# esp_stm_v1.net
KiCad netlist of a schematic drawn in Altium Designer
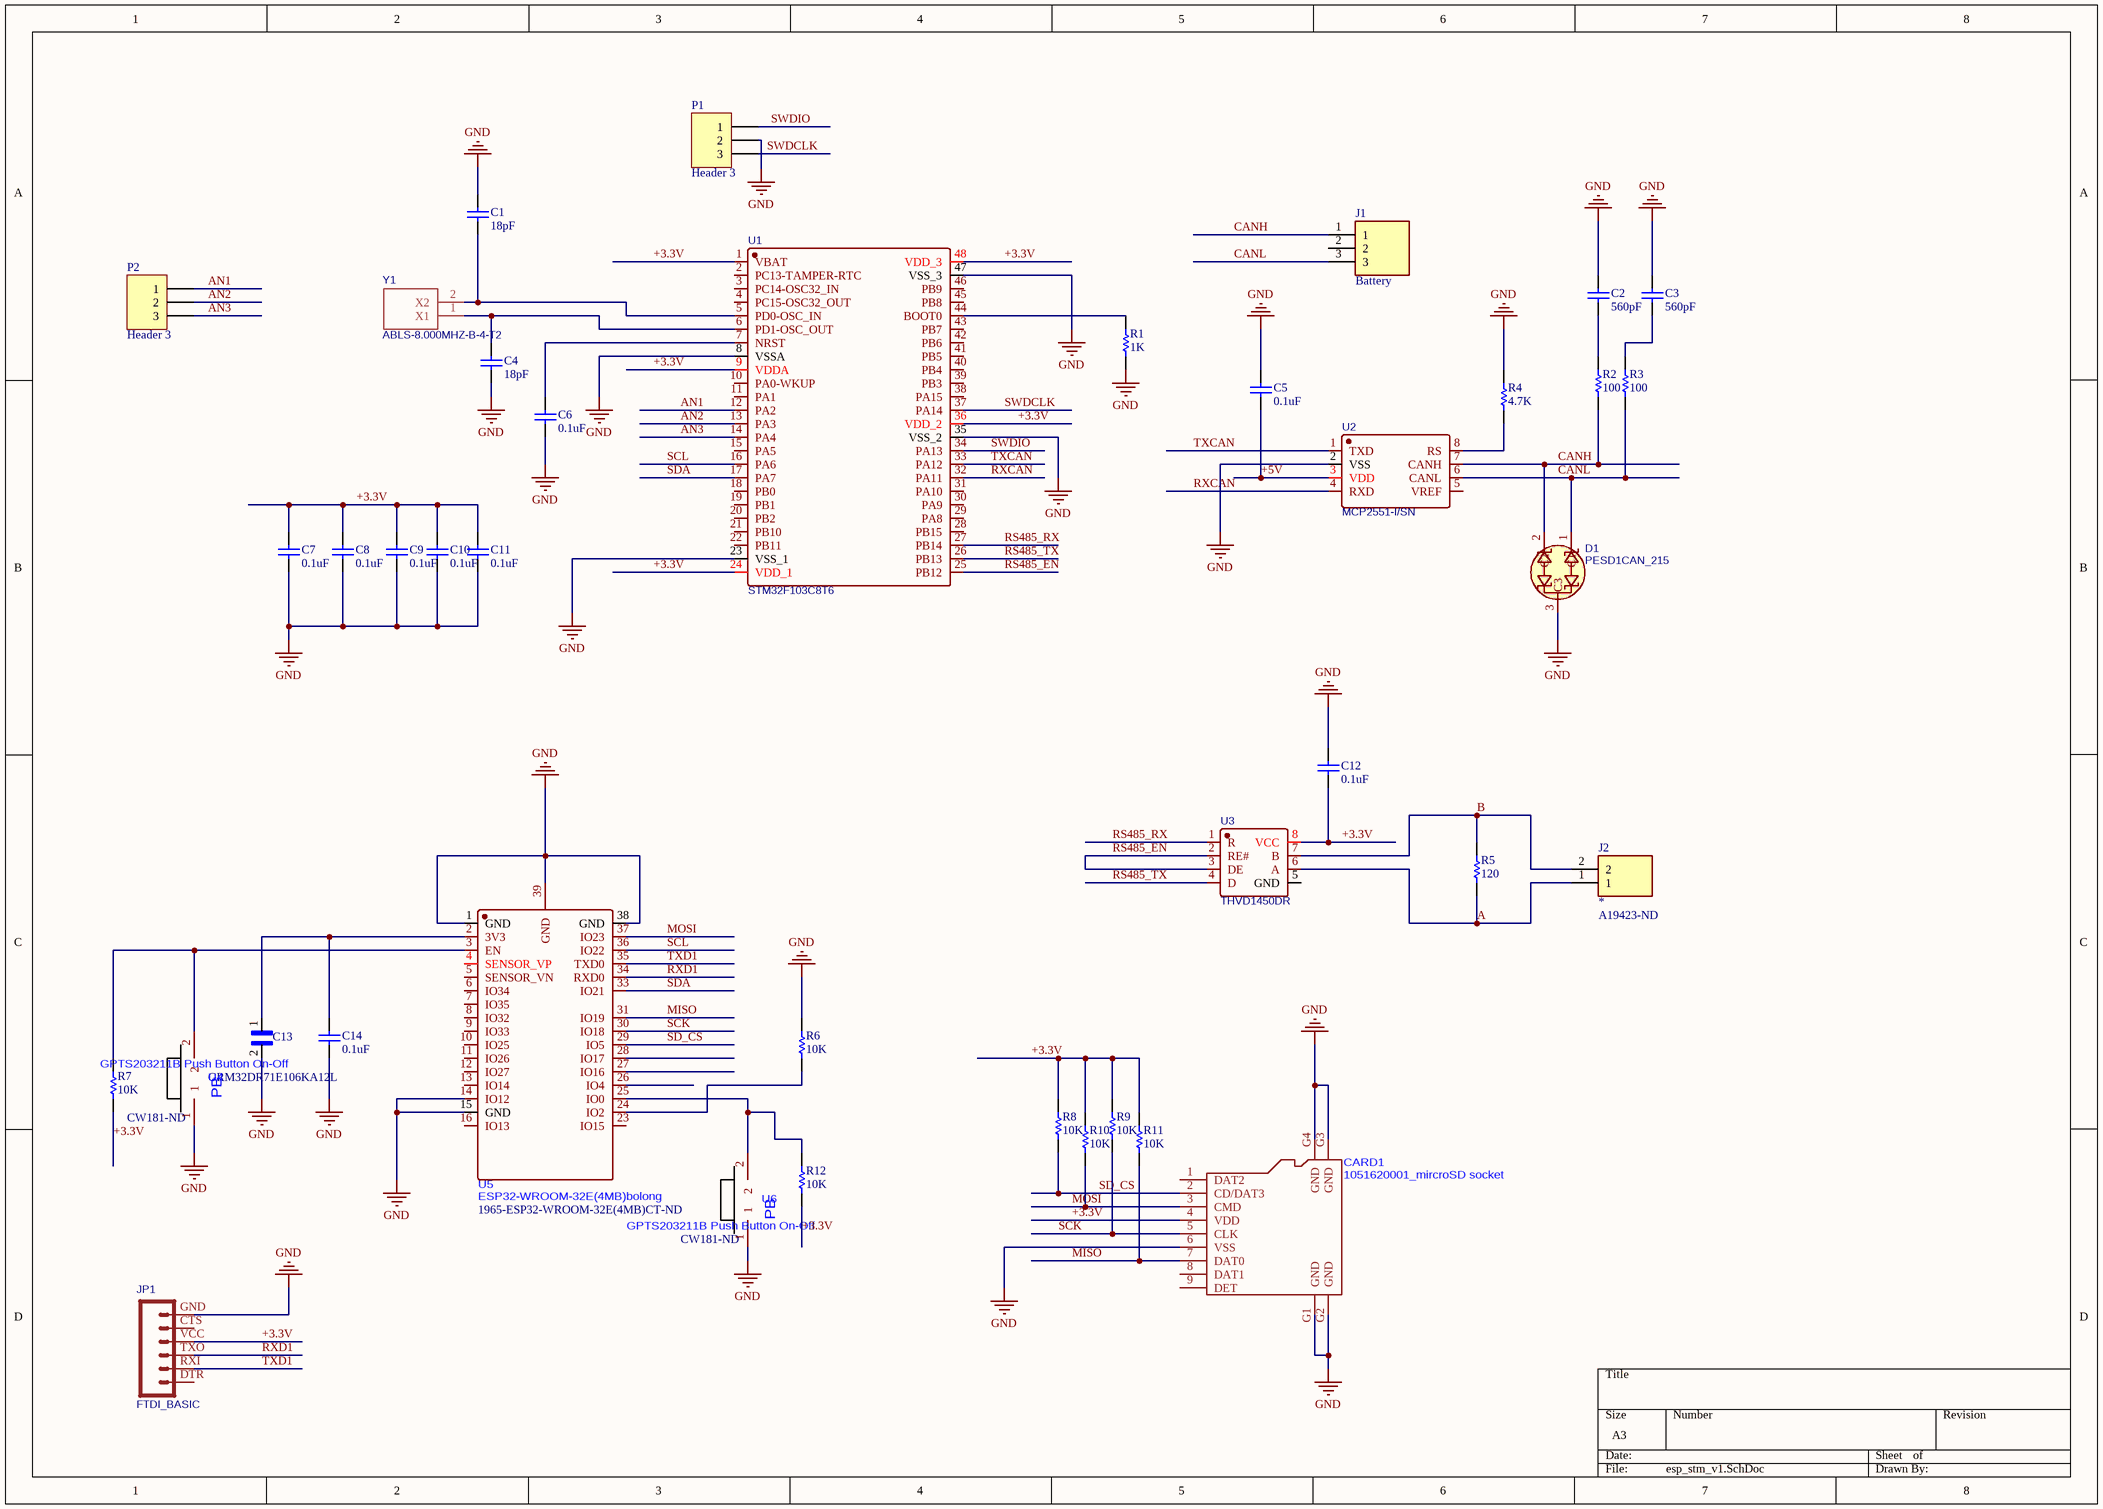
[diagram p0: esp_stm_v1.SchDoc]

(export (version "E")
  (design (tool "Eeschema 10.0.6"))
  (components
    (comp (ref "C1")
      (value "18pF")
      (footprint "1206")
      (description "Capacitor")
      (fields
        (field (name "MANUFACTURE PART NUMBER") "885012208087")
        (field (name "VENDOR PART NUMBER") "732-8127-1-ND")
      )
      (libsource (lib "Miscellaneous Devices") (part "Cap"))
    )
    (comp (ref "C2")
      (value "560pF")
      (footprint "library_v3:SMD-1206-RES")
      (description "Capacitor")
      (fields
        (field (name "MANUFACTURE PART NUMBER") "885012208087")
        (field (name "VENDOR PART NUMBER") "732-8127-1-ND")
      )
      (libsource (lib "Miscellaneous Devices") (part "Cap"))
    )
    (comp (ref "C3")
      (value "560pF")
      (footprint "library_v3:SMD-1206-RES")
      (description "Capacitor")
      (fields
        (field (name "MANUFACTURE PART NUMBER") "885012208087")
        (field (name "VENDOR PART NUMBER") "732-8127-1-ND")
      )
      (libsource (lib "Miscellaneous Devices") (part "Cap"))
    )
    (comp (ref "C4")
      (value "18pF")
      (footprint "1206")
      (description "Capacitor")
      (fields
        (field (name "MANUFACTURE PART NUMBER") "885012208087")
        (field (name "VENDOR PART NUMBER") "732-8127-1-ND")
      )
      (libsource (lib "Miscellaneous Devices") (part "Cap"))
    )
    (comp (ref "C5")
      (value "0.1uF")
      (footprint "library_v3:SMD-1206-RES")
      (description "Capacitor")
      (fields
        (field (name "MANUFACTURE PART NUMBER") "885012208087")
        (field (name "VENDOR PART NUMBER") "732-8127-1-ND")
      )
      (libsource (lib "Miscellaneous Devices") (part "Cap"))
    )
    (comp (ref "C6")
      (value "0.1uF")
      (footprint "1206")
      (description "Capacitor")
      (fields
        (field (name "MANUFACTURE PART NUMBER") "885012208087")
        (field (name "VENDOR PART NUMBER") "732-8127-1-ND")
      )
      (libsource (lib "Miscellaneous Devices") (part "Cap"))
    )
    (comp (ref "C7")
      (value "0.1uF")
      (footprint "1206")
      (description "Capacitor")
      (fields
        (field (name "MANUFACTURE PART NUMBER") "885012208087")
        (field (name "VENDOR PART NUMBER") "732-8127-1-ND")
      )
      (libsource (lib "Miscellaneous Devices") (part "Cap"))
    )
    (comp (ref "C8")
      (value "0.1uF")
      (footprint "1206")
      (description "Capacitor")
      (fields
        (field (name "MANUFACTURE PART NUMBER") "885012208087")
        (field (name "VENDOR PART NUMBER") "732-8127-1-ND")
      )
      (libsource (lib "Miscellaneous Devices") (part "Cap"))
    )
    (comp (ref "C9")
      (value "0.1uF")
      (footprint "1206")
      (description "Capacitor")
      (fields
        (field (name "MANUFACTURE PART NUMBER") "885012208087")
        (field (name "VENDOR PART NUMBER") "732-8127-1-ND")
      )
      (libsource (lib "Miscellaneous Devices") (part "Cap"))
    )
    (comp (ref "C10")
      (value "0.1uF")
      (footprint "1206")
      (description "Capacitor")
      (fields
        (field (name "MANUFACTURE PART NUMBER") "885012208087")
        (field (name "VENDOR PART NUMBER") "732-8127-1-ND")
      )
      (libsource (lib "Miscellaneous Devices") (part "Cap"))
    )
    (comp (ref "C11")
      (value "0.1uF")
      (footprint "1206")
      (description "Capacitor")
      (fields
        (field (name "MANUFACTURE PART NUMBER") "885012208087")
        (field (name "VENDOR PART NUMBER") "732-8127-1-ND")
      )
      (libsource (lib "Miscellaneous Devices") (part "Cap"))
    )
    (comp (ref "C12")
      (value "0.1uF")
      (footprint "SMD-1206-RES")
      (description "Capacitor")
      (fields
        (field (name "MANUFACTURE PART NUMBER") "885012208087")
        (field (name "VENDOR PART NUMBER") "732-8127-1-ND")
      )
      (libsource (lib "Miscellaneous Devices") (part "Cap"))
    )
    (comp (ref "C13")
      (value "GRM32DR71E106KA12L")
      (footprint "CAPC3225X270N")
      (description "SMD Capacitor X7R_EIA_ with Capacitance: 10uF Tol. 10%. Rated Voltage: 25Vdc")
      (fields (field (name "MF") "Murata Electronics"))
      (libsource (lib "library_v3") (part "GRM32DR71E106KA12L"))
    )
    (comp (ref "C14")
      (value "0.1uF")
      (footprint "1206")
      (description "Capacitor")
      (fields
        (field (name "MANUFACTURE PART NUMBER") "885012208087")
        (field (name "VENDOR PART NUMBER") "732-8127-1-ND")
      )
      (libsource (lib "Miscellaneous Devices") (part "Cap"))
    )
    (comp (ref "CARD1")
      (value "1051620001_mircroSD socket")
      (footprint "1051620001 MOLEX")
      (libsource (lib "comp_1") (part "1051620001_mircroSD socket"))
    )
    (comp (ref "D1")
      (value "PESD1CAN_215")
      (footprint "SOT-23-3")
      (fields (field (name "MANUFACTURER") "Nexperia USA Inc.") (field (name "CONTRIBUTOR") "carlo1300"))
      (libsource (lib "comp_1") (part "PESD1CAN_215"))
    )
    (comp (ref "J1")
      (value "PR20203VBNN")
      (footprint "TE_640456-3")
      (description "Connector Header Through Hole 3 position 0.100 _2.54mm_")
      (fields
        (field (name "DIGI-KEY_PART_NUMBER") "1849-1003-ND")
        (field (name "MF") "METZ CONNECT USA Inc.")
        (field (name "COMMENT_1") "Battery")
      )
      (libsource (lib "library_v3") (part "640456-3"))
    )
    (comp (ref "J2")
      (value "640454-2")
      (footprint "TE_640454-2")
      (description "02P MTA100 HDR ASSY SQ STR POL")
      (fields
        (field (name "MF") "TE Connectivity")
        (field (name "DIGI-KEY_PART_NUMBER") "A19439-ND")
        (field (name "COMMENT_1") "*")
        (field (name "SUPPLIER PART NUMBER 1") "A19423-ND")
      )
      (libsource (lib "library_v3") (part "640454-2"))
    )
    (comp (ref "JP1")
      (value "FTDI_BASIC")
      (footprint "FTDI_BASIC")
      (fields (field (name "BOM_MANUFACTURER PART") "?") (field (name "CONTRIBUTOR") "SparkFun"))
      (libsource (lib "library_v3") (part "FTDI_BASIC"))
    )
    (comp (ref "P1")
      (value "Header 3")
      (footprint "HDR1X3")
      (description "Header, 3-Pin")
      (fields (field (name "PUBLISHER") "Altium Limited"))
      (libsource (lib "Miscellaneous Connectors") (part "Header 3"))
    )
    (comp (ref "P2")
      (value "Header 3")
      (footprint "HDR1X3")
      (description "Header, 3-Pin")
      (fields (field (name "PUBLISHER") "Altium Limited"))
      (libsource (lib "Miscellaneous Connectors") (part "Header 3"))
    )
    (comp (ref "R1")
      (value "1K")
      (footprint "1206")
      (description "Semiconductor Resistor")
      (fields
        (field (name "MANUFACTURE PART NUMBER") "RC1206JR-0710KL")
        (field (name "VENDOR PART NUMBER") "311-10KERCT-ND")
      )
      (libsource (lib "Miscellaneous Devices") (part "Res Semi"))
    )
    (comp (ref "R2")
      (value "100")
      (footprint "library_v3:SMD-1206-RES")
      (description "Semiconductor Resistor")
      (fields
        (field (name "MANUFACTURE PART NUMBER") "RC1206JR-0710KL")
        (field (name "VENDOR PART NUMBER") "311-10KERCT-ND")
      )
      (libsource (lib "Miscellaneous Devices") (part "Res Semi"))
    )
    (comp (ref "R3")
      (value "100")
      (footprint "library_v3:SMD-1206-RES")
      (description "Semiconductor Resistor")
      (fields
        (field (name "MANUFACTURE PART NUMBER") "RC1206JR-0710KL")
        (field (name "VENDOR PART NUMBER") "311-10KERCT-ND")
      )
      (libsource (lib "Miscellaneous Devices") (part "Res Semi"))
    )
    (comp (ref "R4")
      (value "4.7K")
      (footprint "library_v3:SMD-1206-RES")
      (description "Semiconductor Resistor")
      (fields
        (field (name "MANUFACTURE PART NUMBER") "RC1206JR-0710KL")
        (field (name "VENDOR PART NUMBER") "311-10KERCT-ND")
      )
      (libsource (lib "Miscellaneous Devices") (part "Res Semi"))
    )
    (comp (ref "R5")
      (value "120")
      (footprint "SMD-1206-RES")
      (description "Semiconductor Resistor")
      (fields
        (field (name "MANUFACTURE PART NUMBER") "RC1206JR-0710KL")
        (field (name "VENDOR PART NUMBER") "311-10KERCT-ND")
      )
      (libsource (lib "*") (part "Res Semi"))
    )
    (comp (ref "R6")
      (value "10K")
      (footprint "1206")
      (description "Semiconductor Resistor")
      (fields
        (field (name "MANUFACTURE PART NUMBER") "RC1206JR-0710KL")
        (field (name "VENDOR PART NUMBER") "311-10KERCT-ND")
      )
      (libsource (lib "Miscellaneous Devices") (part "Res Semi"))
    )
    (comp (ref "R7")
      (value "10K")
      (footprint "1206")
      (description "Semiconductor Resistor")
      (fields
        (field (name "MANUFACTURE PART NUMBER") "RC1206JR-0710KL")
        (field (name "VENDOR PART NUMBER") "311-10KERCT-ND")
      )
      (libsource (lib "Miscellaneous Devices") (part "Res Semi"))
    )
    (comp (ref "R8")
      (value "10K")
      (footprint "1206")
      (description "Semiconductor Resistor")
      (fields
        (field (name "MANUFACTURE PART NUMBER") "RC1206JR-0710KL")
        (field (name "VENDOR PART NUMBER") "311-10KERCT-ND")
      )
      (libsource (lib "Miscellaneous Devices") (part "Res Semi"))
    )
    (comp (ref "R9")
      (value "10K")
      (footprint "1206")
      (description "Semiconductor Resistor")
      (fields
        (field (name "MANUFACTURE PART NUMBER") "RC1206JR-0710KL")
        (field (name "VENDOR PART NUMBER") "311-10KERCT-ND")
      )
      (libsource (lib "Miscellaneous Devices") (part "Res Semi"))
    )
    (comp (ref "R10")
      (value "10K")
      (footprint "1206")
      (description "Semiconductor Resistor")
      (fields
        (field (name "MANUFACTURE PART NUMBER") "RC1206JR-0710KL")
        (field (name "VENDOR PART NUMBER") "311-10KERCT-ND")
      )
      (libsource (lib "Miscellaneous Devices") (part "Res Semi"))
    )
    (comp (ref "R11")
      (value "10K")
      (footprint "1206")
      (description "Semiconductor Resistor")
      (fields
        (field (name "MANUFACTURE PART NUMBER") "RC1206JR-0710KL")
        (field (name "VENDOR PART NUMBER") "311-10KERCT-ND")
      )
      (libsource (lib "Miscellaneous Devices") (part "Res Semi"))
    )
    (comp (ref "R12")
      (value "10K")
      (footprint "1206")
      (description "Semiconductor Resistor")
      (fields
        (field (name "MANUFACTURE PART NUMBER") "RC1206JR-0710KL")
        (field (name "VENDOR PART NUMBER") "311-10KERCT-ND")
      )
      (libsource (lib "Miscellaneous Devices") (part "Res Semi"))
    )
    (comp (ref "U1")
      (value "STM32F103C8T6")
      (footprint "LQFP-48_L7.0-W7.0-P0.50-LS9.0-BL")
      (fields (field (name "MANUFACTURER") "ST(意法半导体)"))
      (libsource (lib "component_lib_v1") (part "STM32F103C8T6"))
    )
    (comp (ref "U2")
      (value "MCP2551-I/SN")
      (footprint "SOIC8-1.27-5X4MM")
      (fields (field (name "BOM_SUPPLIER PART") "C7376"))
      (libsource (lib "comp_1") (part "MCP2551-I/SN"))
    )
    (comp (ref "U3")
      (value "THVD1450DR")
      (footprint "SOIC-8_L4.9-W3.9-P1.27-LS6.0-BL")
      (fields (field (name "MANUFACTURER") "TI(????)") (field (name "CONTRIBUTOR") "LCSC"))
      (libsource (lib "component_lib_v1") (part "THVD1450DR"))
    )
    (comp (ref "U4")
      (value "GPTS203211B Push Button On-Off")
      (footprint "GPTS203211B-PUSHBUTTON-ON-OFF")
      (fields (field (name "SUPPLIER PART NUMBER 1") "CW181-ND"))
      (libsource (lib "comp_1") (part "GPTS203211B Push Button On-Off"))
    )
    (comp (ref "U5")
      (value "ESP32-WROOM-32E(4MB)bolong")
      (footprint "WIFI-SMD_ESP32-WROOM-32E")
      (fields (field (name "SUPPLIER PART NUMBER 1") "1965-ESP32-WROOM-32E(4MB)CT-ND"))
      (libsource (lib "comp_1") (part "ESP32-WROOM-32E(4MB)bolong"))
    )
    (comp (ref "U6")
      (value "GPTS203211B Push Button On-Off")
      (footprint "GPTS203211B-PUSHBUTTON-ON-OFF")
      (fields (field (name "SUPPLIER PART NUMBER 1") "CW181-ND"))
      (libsource (lib "comp_1") (part "GPTS203211B Push Button On-Off"))
    )
    (comp (ref "Y1")
      (value "ABLS-8.000MHZ-B-4-T2")
      (footprint "ABLS8000MHZB4T2")
      (fields (field (name "CONTRIBUTOR") "Metin Akin"))
      (libsource (lib "library_v3") (part "ABLS-8.000MHZ-B-4-T2"))
    )
  )
  (nets
    (net (code "1") (name "/+3.3V") (class "Default")
      (node (ref "C10") (pin "1") (pinfunction "1_1") (pintype "passive"))
      (node (ref "C11") (pin "1") (pinfunction "1_1") (pintype "passive"))
      (node (ref "C12") (pin "2") (pinfunction "2_2") (pintype "passive"))
      (node (ref "C7") (pin "1") (pinfunction "1_1") (pintype "passive"))
      (node (ref "C8") (pin "1") (pinfunction "1_1") (pintype "passive"))
      (node (ref "C9") (pin "1") (pinfunction "1_1") (pintype "passive"))
      (node (ref "CARD1") (pin "4") (pinfunction "VDD_4") (pintype "passive"))
      (node (ref "JP1") (pin "VCC") (pinfunction "4_VCC") (pintype "passive"))
      (node (ref "R10") (pin "1") (pinfunction "1_1") (pintype "passive"))
      (node (ref "R11") (pin "1") (pinfunction "1_1") (pintype "passive"))
      (node (ref "R12") (pin "2") (pinfunction "2_2") (pintype "passive"))
      (node (ref "R7") (pin "2") (pinfunction "2_2") (pintype "passive"))
      (node (ref "R8") (pin "1") (pinfunction "1_1") (pintype "passive"))
      (node (ref "R9") (pin "1") (pinfunction "1_1") (pintype "passive"))
      (node (ref "U1") (pin "1") (pinfunction "VBAT_1") (pintype "passive"))
      (node (ref "U1") (pin "24") (pinfunction "VDD_1_24") (pintype "passive"))
      (node (ref "U1") (pin "36") (pinfunction "VDD_2_36") (pintype "passive"))
      (node (ref "U1") (pin "48") (pinfunction "VDD_3_48") (pintype "passive"))
      (node (ref "U1") (pin "9") (pinfunction "VDDA_9") (pintype "passive"))
      (node (ref "U3") (pin "8") (pinfunction "VCC_8") (pintype "passive"))
    )
    (net (code "2") (name "/+5V") (class "Default")
      (node (ref "C5") (pin "2") (pinfunction "2_2") (pintype "passive"))
      (node (ref "U2") (pin "3") (pinfunction "VDD_3") (pintype "passive"))
    )
    (net (code "3") (name "/A") (class "Default")
      (node (ref "J2") (pin "1") (pinfunction "1_1") (pintype "passive"))
      (node (ref "R5") (pin "2") (pinfunction "2_2") (pintype "passive"))
      (node (ref "U3") (pin "6") (pinfunction "A_6") (pintype "passive"))
    )
    (net (code "4") (name "/AN1") (class "Default")
      (node (ref "P2") (pin "1") (pinfunction "1_1") (pintype "passive"))
      (node (ref "U1") (pin "12") (pinfunction "PA2_12") (pintype "passive"))
    )
    (net (code "5") (name "/AN2") (class "Default")
      (node (ref "P2") (pin "2") (pinfunction "2_2") (pintype "passive"))
      (node (ref "U1") (pin "13") (pinfunction "PA3_13") (pintype "passive"))
    )
    (net (code "6") (name "/AN3") (class "Default")
      (node (ref "P2") (pin "3") (pinfunction "3_3") (pintype "passive"))
      (node (ref "U1") (pin "14") (pinfunction "PA4_14") (pintype "passive"))
    )
    (net (code "7") (name "/B") (class "Default")
      (node (ref "J2") (pin "2") (pinfunction "2_2") (pintype "passive"))
      (node (ref "R5") (pin "1") (pinfunction "1_1") (pintype "passive"))
      (node (ref "U3") (pin "7") (pinfunction "B_7") (pintype "passive"))
    )
    (net (code "8") (name "/CANH") (class "Default")
      (node (ref "D1") (pin "2") (pinfunction "C2_2") (pintype "passive"))
      (node (ref "J1") (pin "1") (pinfunction "1_1") (pintype "passive"))
      (node (ref "R2") (pin "1") (pinfunction "1_1") (pintype "passive"))
      (node (ref "U2") (pin "7") (pinfunction "CANH_7") (pintype "passive"))
    )
    (net (code "9") (name "/CANL") (class "Default")
      (node (ref "D1") (pin "1") (pinfunction "C1_1") (pintype "passive"))
      (node (ref "J1") (pin "3") (pinfunction "3_3") (pintype "passive"))
      (node (ref "R3") (pin "1") (pinfunction "1_1") (pintype "passive"))
      (node (ref "U2") (pin "6") (pinfunction "CANL_6") (pintype "passive"))
    )
    (net (code "10") (name "/MISO") (class "Default")
      (node (ref "CARD1") (pin "7") (pinfunction "DAT0_7") (pintype "passive"))
      (node (ref "R11") (pin "2") (pinfunction "2_2") (pintype "passive"))
      (node (ref "U5") (pin "31") (pinfunction "IO19_31") (pintype "passive"))
    )
    (net (code "11") (name "/MOSI") (class "Default")
      (node (ref "CARD1") (pin "3") (pinfunction "CMD_3") (pintype "passive"))
      (node (ref "R10") (pin "2") (pinfunction "2_2") (pintype "passive"))
      (node (ref "U5") (pin "37") (pinfunction "IO23_37") (pintype "passive"))
    )
    (net (code "12") (name "/RS485_EN") (class "Default")
      (node (ref "U1") (pin "25") (pinfunction "PB12_25") (pintype "passive"))
      (node (ref "U3") (pin "2") (pinfunction "RE#_2") (pintype "passive"))
      (node (ref "U3") (pin "3") (pinfunction "DE_3") (pintype "passive"))
    )
    (net (code "13") (name "/RS485_RX") (class "Default")
      (node (ref "U1") (pin "27") (pinfunction "PB14_27") (pintype "passive"))
      (node (ref "U3") (pin "1") (pinfunction "R_1") (pintype "passive"))
    )
    (net (code "14") (name "/RS485_TX") (class "Default")
      (node (ref "U1") (pin "26") (pinfunction "PB13_26") (pintype "passive"))
      (node (ref "U3") (pin "4") (pinfunction "D_4") (pintype "passive"))
    )
    (net (code "15") (name "/RXCAN") (class "Default")
      (node (ref "U1") (pin "32") (pinfunction "PA11_32") (pintype "passive"))
      (node (ref "U2") (pin "4") (pinfunction "RXD_4") (pintype "passive"))
    )
    (net (code "16") (name "/RXD1") (class "Default")
      (node (ref "JP1") (pin "TXO") (pinfunction "3_TXO") (pintype "passive"))
      (node (ref "U5") (pin "34") (pinfunction "RXD0_34") (pintype "passive"))
    )
    (net (code "17") (name "/SCK") (class "Default")
      (node (ref "CARD1") (pin "5") (pinfunction "CLK_5") (pintype "passive"))
      (node (ref "R9") (pin "2") (pinfunction "2_2") (pintype "passive"))
      (node (ref "U5") (pin "30") (pinfunction "IO18_30") (pintype "passive"))
    )
    (net (code "18") (name "/SCL") (class "Default")
      (node (ref "U1") (pin "16") (pinfunction "PA6_16") (pintype "passive"))
      (node (ref "U5") (pin "36") (pinfunction "IO22_36") (pintype "passive"))
    )
    (net (code "19") (name "/SDA") (class "Default")
      (node (ref "U1") (pin "17") (pinfunction "PA7_17") (pintype "passive"))
      (node (ref "U5") (pin "33") (pinfunction "IO21_33") (pintype "passive"))
    )
    (net (code "20") (name "/SD_CS") (class "Default")
      (node (ref "CARD1") (pin "2") (pinfunction "CD/DAT3_2") (pintype "passive"))
      (node (ref "R8") (pin "2") (pinfunction "2_2") (pintype "passive"))
      (node (ref "U5") (pin "29") (pinfunction "IO5_29") (pintype "passive"))
    )
    (net (code "21") (name "/SWDCLK") (class "Default")
      (node (ref "P1") (pin "3") (pinfunction "3_3") (pintype "passive"))
      (node (ref "U1") (pin "37") (pinfunction "PA14_37") (pintype "passive"))
    )
    (net (code "22") (name "/SWDIO") (class "Default")
      (node (ref "P1") (pin "1") (pinfunction "1_1") (pintype "passive"))
      (node (ref "U1") (pin "34") (pinfunction "PA13_34") (pintype "passive"))
    )
    (net (code "23") (name "/TXCAN") (class "Default")
      (node (ref "U1") (pin "33") (pinfunction "PA12_33") (pintype "passive"))
      (node (ref "U2") (pin "1") (pinfunction "TXD_1") (pintype "passive"))
    )
    (net (code "24") (name "/TXD1") (class "Default")
      (node (ref "JP1") (pin "RXI") (pinfunction "2_RXI") (pintype "passive"))
      (node (ref "U5") (pin "35") (pinfunction "TXD0_35") (pintype "passive"))
    )
    (net (code "25") (name "GND") (class "Default")
      (node (ref "C1") (pin "1") (pinfunction "1_1") (pintype "passive"))
      (node (ref "C10") (pin "2") (pinfunction "2_2") (pintype "passive"))
      (node (ref "C11") (pin "2") (pinfunction "2_2") (pintype "passive"))
      (node (ref "C12") (pin "1") (pinfunction "1_1") (pintype "passive"))
      (node (ref "C13") (pin "2") (pinfunction "2_2") (pintype "passive"))
      (node (ref "C14") (pin "2") (pinfunction "2_2") (pintype "passive"))
      (node (ref "C2") (pin "1") (pinfunction "1_1") (pintype "passive"))
      (node (ref "C3") (pin "1") (pinfunction "1_1") (pintype "passive"))
      (node (ref "C4") (pin "2") (pinfunction "2_2") (pintype "passive"))
      (node (ref "C5") (pin "1") (pinfunction "1_1") (pintype "passive"))
      (node (ref "C6") (pin "2") (pinfunction "2_2") (pintype "passive"))
      (node (ref "C7") (pin "2") (pinfunction "2_2") (pintype "passive"))
      (node (ref "C8") (pin "2") (pinfunction "2_2") (pintype "passive"))
      (node (ref "C9") (pin "2") (pinfunction "2_2") (pintype "passive"))
      (node (ref "CARD1") (pin "6") (pinfunction "VSS_6") (pintype "passive"))
      (node (ref "CARD1") (pin "G1") (pinfunction "GND_G1") (pintype "passive"))
      (node (ref "CARD1") (pin "G2") (pinfunction "GND_G2") (pintype "passive"))
      (node (ref "CARD1") (pin "G3") (pinfunction "GND_G3") (pintype "passive"))
      (node (ref "CARD1") (pin "G4") (pinfunction "GND_G4") (pintype "passive"))
      (node (ref "D1") (pin "3") (pinfunction "C3_3") (pintype "passive"))
      (node (ref "JP1") (pin "GND") (pinfunction "6_GND") (pintype "passive"))
      (node (ref "P1") (pin "2") (pinfunction "2_2") (pintype "passive"))
      (node (ref "R1") (pin "2") (pinfunction "2_2") (pintype "passive"))
      (node (ref "R4") (pin "2") (pinfunction "2_2") (pintype "passive"))
      (node (ref "R6") (pin "1") (pinfunction "1_1") (pintype "passive"))
      (node (ref "U1") (pin "23") (pinfunction "VSS_1_23") (pintype "passive"))
      (node (ref "U1") (pin "35") (pinfunction "VSS_2_35") (pintype "passive"))
      (node (ref "U1") (pin "47") (pinfunction "VSS_3_47") (pintype "passive"))
      (node (ref "U1") (pin "8") (pinfunction "VSSA_8") (pintype "passive"))
      (node (ref "U2") (pin "2") (pinfunction "VSS_2") (pintype "passive"))
      (node (ref "U4") (pin "1") (pinfunction "1_1") (pintype "passive"))
      (node (ref "U5") (pin "1") (pinfunction "GND_1") (pintype "passive"))
      (node (ref "U5") (pin "14") (pinfunction "IO12_14") (pintype "passive"))
      (node (ref "U5") (pin "15") (pinfunction "GND_15") (pintype "passive"))
      (node (ref "U5") (pin "38") (pinfunction "GND_38") (pintype "passive"))
      (node (ref "U5") (pin "39") (pinfunction "GND_39") (pintype "passive"))
      (node (ref "U6") (pin "1") (pinfunction "1_1") (pintype "passive"))
    )
    (net (code "26") (name "Net-(C2-Pad2)") (class "Default")
      (node (ref "C2") (pin "2") (pinfunction "2_2") (pintype "passive"))
      (node (ref "R2") (pin "2") (pinfunction "2_2") (pintype "passive"))
    )
    (net (code "27") (name "Net-(C3-Pad2)") (class "Default")
      (node (ref "C3") (pin "2") (pinfunction "2_2") (pintype "passive"))
      (node (ref "R3") (pin "2") (pinfunction "2_2") (pintype "passive"))
    )
    (net (code "28") (name "Net-(U1-BOOT0)") (class "Default")
      (node (ref "R1") (pin "1") (pinfunction "1_1") (pintype "passive"))
      (node (ref "U1") (pin "44") (pinfunction "BOOT0_44") (pintype "passive"))
    )
    (net (code "29") (name "Net-(U1-NRST)") (class "Default")
      (node (ref "C6") (pin "1") (pinfunction "1_1") (pintype "passive"))
      (node (ref "U1") (pin "7") (pinfunction "NRST_7") (pintype "passive"))
    )
    (net (code "30") (name "Net-(U1-PD0-OSC_IN)") (class "Default")
      (node (ref "C1") (pin "2") (pinfunction "2_2") (pintype "passive"))
      (node (ref "U1") (pin "5") (pinfunction "PD0-OSC_IN_5") (pintype "passive"))
      (node (ref "Y1") (pin "2") (pinfunction "X2_2") (pintype "passive"))
    )
    (net (code "31") (name "Net-(U1-PD1-OSC_OUT)") (class "Default")
      (node (ref "C4") (pin "1") (pinfunction "1_1") (pintype "passive"))
      (node (ref "U1") (pin "6") (pinfunction "PD1-OSC_OUT_6") (pintype "passive"))
      (node (ref "Y1") (pin "1") (pinfunction "X1_1") (pintype "passive"))
    )
    (net (code "32") (name "Net-(U2-RS)") (class "Default")
      (node (ref "R4") (pin "1") (pinfunction "1_1") (pintype "passive"))
      (node (ref "U2") (pin "8") (pinfunction "RS_8") (pintype "passive"))
    )
    (net (code "33") (name "Net-(U5-3V3)") (class "Default")
      (node (ref "C13") (pin "1") (pinfunction "1_1") (pintype "passive"))
      (node (ref "C14") (pin "1") (pinfunction "1_1") (pintype "passive"))
      (node (ref "U5") (pin "2") (pinfunction "3V3_2") (pintype "passive"))
    )
    (net (code "34") (name "Net-(U5-EN)") (class "Default")
      (node (ref "R7") (pin "1") (pinfunction "1_1") (pintype "passive"))
      (node (ref "U4") (pin "2") (pinfunction "2_2") (pintype "passive"))
      (node (ref "U5") (pin "3") (pinfunction "EN_3") (pintype "passive"))
    )
    (net (code "35") (name "Net-(U5-IO0)") (class "Default")
      (node (ref "R12") (pin "1") (pinfunction "1_1") (pintype "passive"))
      (node (ref "U5") (pin "25") (pinfunction "IO0_25") (pintype "passive"))
      (node (ref "U6") (pin "2") (pinfunction "2_2") (pintype "passive"))
    )
    (net (code "36") (name "Net-(U5-IO2)") (class "Default")
      (node (ref "R6") (pin "2") (pinfunction "2_2") (pintype "passive"))
      (node (ref "U5") (pin "24") (pinfunction "IO2_24") (pintype "passive"))
    )
    (net (code "37") (name "unconnected-(CARD1-DAT1-Pad8)") (class "Default")
      (node (ref "CARD1") (pin "8") (pinfunction "DAT1_8") (pintype "passive"))
    )
    (net (code "38") (name "unconnected-(CARD1-DAT2-Pad1)") (class "Default")
      (node (ref "CARD1") (pin "1") (pinfunction "DAT2_1") (pintype "passive"))
    )
    (net (code "39") (name "unconnected-(CARD1-DET-Pad9)") (class "Default")
      (node (ref "CARD1") (pin "9") (pinfunction "DET_9") (pintype "passive"))
    )
    (net (code "40") (name "unconnected-(J1-Pad2)") (class "Default")
      (node (ref "J1") (pin "2") (pinfunction "2_2") (pintype "passive"))
    )
    (net (code "41") (name "unconnected-(JP1-1-PadDTR)") (class "Default")
      (node (ref "JP1") (pin "DTR") (pinfunction "1_DTR") (pintype "passive"))
    )
    (net (code "42") (name "unconnected-(JP1-5-PadCTS)") (class "Default")
      (node (ref "JP1") (pin "CTS") (pinfunction "5_CTS") (pintype "passive"))
    )
    (net (code "43") (name "unconnected-(U1-PA0-WKUP-Pad10)") (class "Default")
      (node (ref "U1") (pin "10") (pinfunction "PA0-WKUP_10") (pintype "passive"))
    )
    (net (code "44") (name "unconnected-(U1-PA1-Pad11)") (class "Default")
      (node (ref "U1") (pin "11") (pinfunction "PA1_11") (pintype "passive"))
    )
    (net (code "45") (name "unconnected-(U1-PA5-Pad15)") (class "Default")
      (node (ref "U1") (pin "15") (pinfunction "PA5_15") (pintype "passive"))
    )
    (net (code "46") (name "unconnected-(U1-PA8-Pad29)") (class "Default")
      (node (ref "U1") (pin "29") (pinfunction "PA8_29") (pintype "passive"))
    )
    (net (code "47") (name "unconnected-(U1-PA9-Pad30)") (class "Default")
      (node (ref "U1") (pin "30") (pinfunction "PA9_30") (pintype "passive"))
    )
    (net (code "48") (name "unconnected-(U1-PA10-Pad31)") (class "Default")
      (node (ref "U1") (pin "31") (pinfunction "PA10_31") (pintype "passive"))
    )
    (net (code "49") (name "unconnected-(U1-PA15-Pad38)") (class "Default")
      (node (ref "U1") (pin "38") (pinfunction "PA15_38") (pintype "passive"))
    )
    (net (code "50") (name "unconnected-(U1-PB0-Pad18)") (class "Default")
      (node (ref "U1") (pin "18") (pinfunction "PB0_18") (pintype "passive"))
    )
    (net (code "51") (name "unconnected-(U1-PB1-Pad19)") (class "Default")
      (node (ref "U1") (pin "19") (pinfunction "PB1_19") (pintype "passive"))
    )
    (net (code "52") (name "unconnected-(U1-PB2-Pad20)") (class "Default")
      (node (ref "U1") (pin "20") (pinfunction "PB2_20") (pintype "passive"))
    )
    (net (code "53") (name "unconnected-(U1-PB3-Pad39)") (class "Default")
      (node (ref "U1") (pin "39") (pinfunction "PB3_39") (pintype "passive"))
    )
    (net (code "54") (name "unconnected-(U1-PB4-Pad40)") (class "Default")
      (node (ref "U1") (pin "40") (pinfunction "PB4_40") (pintype "passive"))
    )
    (net (code "55") (name "unconnected-(U1-PB5-Pad41)") (class "Default")
      (node (ref "U1") (pin "41") (pinfunction "PB5_41") (pintype "passive"))
    )
    (net (code "56") (name "unconnected-(U1-PB6-Pad42)") (class "Default")
      (node (ref "U1") (pin "42") (pinfunction "PB6_42") (pintype "passive"))
    )
    (net (code "57") (name "unconnected-(U1-PB7-Pad43)") (class "Default")
      (node (ref "U1") (pin "43") (pinfunction "PB7_43") (pintype "passive"))
    )
    (net (code "58") (name "unconnected-(U1-PB8-Pad45)") (class "Default")
      (node (ref "U1") (pin "45") (pinfunction "PB8_45") (pintype "passive"))
    )
    (net (code "59") (name "unconnected-(U1-PB9-Pad46)") (class "Default")
      (node (ref "U1") (pin "46") (pinfunction "PB9_46") (pintype "passive"))
    )
    (net (code "60") (name "unconnected-(U1-PB10-Pad21)") (class "Default")
      (node (ref "U1") (pin "21") (pinfunction "PB10_21") (pintype "passive"))
    )
    (net (code "61") (name "unconnected-(U1-PB11-Pad22)") (class "Default")
      (node (ref "U1") (pin "22") (pinfunction "PB11_22") (pintype "passive"))
    )
    (net (code "62") (name "unconnected-(U1-PB15-Pad28)") (class "Default")
      (node (ref "U1") (pin "28") (pinfunction "PB15_28") (pintype "passive"))
    )
    (net (code "63") (name "unconnected-(U1-PC13-TAMPER-RTC-Pad2)") (class "Default")
      (node (ref "U1") (pin "2") (pinfunction "PC13-TAMPER-RTC_2") (pintype "passive"))
    )
    (net (code "64") (name "unconnected-(U1-PC14-OSC32_IN-Pad3)") (class "Default")
      (node (ref "U1") (pin "3") (pinfunction "PC14-OSC32_IN_3") (pintype "passive"))
    )
    (net (code "65") (name "unconnected-(U1-PC15-OSC32_OUT-Pad4)") (class "Default")
      (node (ref "U1") (pin "4") (pinfunction "PC15-OSC32_OUT_4") (pintype "passive"))
    )
    (net (code "66") (name "unconnected-(U2-VREF-Pad5)") (class "Default")
      (node (ref "U2") (pin "5") (pinfunction "VREF_5") (pintype "passive"))
    )
    (net (code "67") (name "unconnected-(U3-GND-Pad5)") (class "Default")
      (node (ref "U3") (pin "5") (pinfunction "GND_5") (pintype "passive"))
    )
    (net (code "68") (name "unconnected-(U5-IO4-Pad26)") (class "Default")
      (node (ref "U5") (pin "26") (pinfunction "IO4_26") (pintype "passive"))
    )
    (net (code "69") (name "unconnected-(U5-IO13-Pad16)") (class "Default")
      (node (ref "U5") (pin "16") (pinfunction "IO13_16") (pintype "passive"))
    )
    (net (code "70") (name "unconnected-(U5-IO14-Pad13)") (class "Default")
      (node (ref "U5") (pin "13") (pinfunction "IO14_13") (pintype "passive"))
    )
    (net (code "71") (name "unconnected-(U5-IO15-Pad23)") (class "Default")
      (node (ref "U5") (pin "23") (pinfunction "IO15_23") (pintype "passive"))
    )
    (net (code "72") (name "unconnected-(U5-IO16-Pad27)") (class "Default")
      (node (ref "U5") (pin "27") (pinfunction "IO16_27") (pintype "passive"))
    )
    (net (code "73") (name "unconnected-(U5-IO17-Pad28)") (class "Default")
      (node (ref "U5") (pin "28") (pinfunction "IO17_28") (pintype "passive"))
    )
    (net (code "74") (name "unconnected-(U5-IO25-Pad10)") (class "Default")
      (node (ref "U5") (pin "10") (pinfunction "IO25_10") (pintype "passive"))
    )
    (net (code "75") (name "unconnected-(U5-IO26-Pad11)") (class "Default")
      (node (ref "U5") (pin "11") (pinfunction "IO26_11") (pintype "passive"))
    )
    (net (code "76") (name "unconnected-(U5-IO27-Pad12)") (class "Default")
      (node (ref "U5") (pin "12") (pinfunction "IO27_12") (pintype "passive"))
    )
    (net (code "77") (name "unconnected-(U5-IO32-Pad8)") (class "Default")
      (node (ref "U5") (pin "8") (pinfunction "IO32_8") (pintype "passive"))
    )
    (net (code "78") (name "unconnected-(U5-IO33-Pad9)") (class "Default")
      (node (ref "U5") (pin "9") (pinfunction "IO33_9") (pintype "passive"))
    )
    (net (code "79") (name "unconnected-(U5-IO34-Pad6)") (class "Default")
      (node (ref "U5") (pin "6") (pinfunction "IO34_6") (pintype "passive"))
    )
    (net (code "80") (name "unconnected-(U5-IO35-Pad7)") (class "Default")
      (node (ref "U5") (pin "7") (pinfunction "IO35_7") (pintype "passive"))
    )
    (net (code "81") (name "unconnected-(U5-SENSOR_VN-Pad5)") (class "Default")
      (node (ref "U5") (pin "5") (pinfunction "SENSOR_VN_5") (pintype "passive"))
    )
    (net (code "82") (name "unconnected-(U5-SENSOR_VP-Pad4)") (class "Default")
      (node (ref "U5") (pin "4") (pinfunction "SENSOR_VP_4") (pintype "passive"))
    )
  )
)
